# Schematic_v20.net
KiCad netlist of a schematic drawn in EAGLE
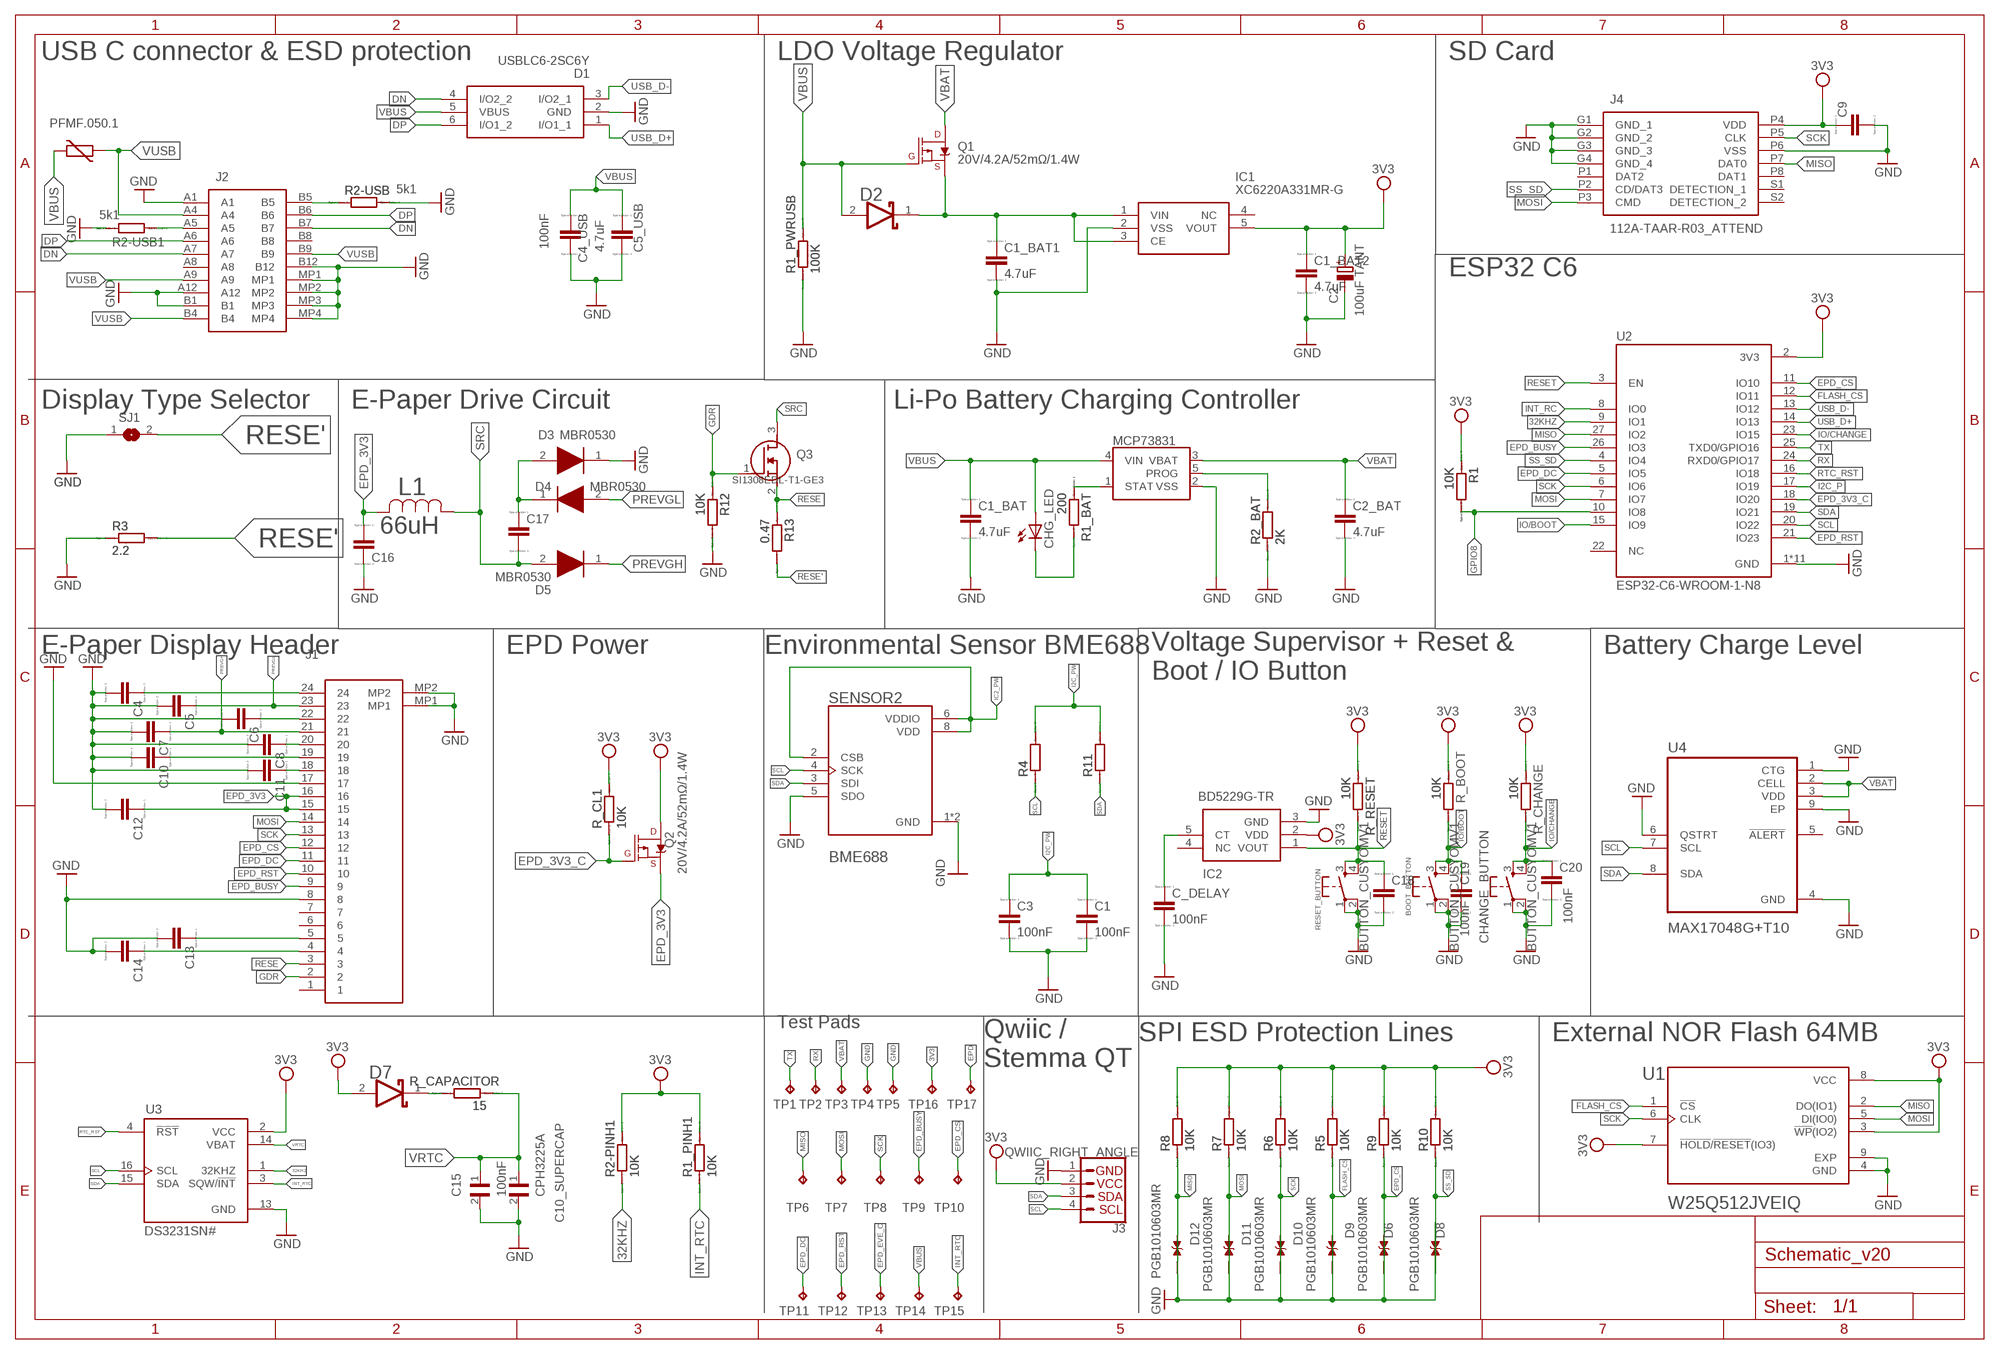
[diagram p0: schematic, sheet 1]

(export (version "E")
  (design (tool "Eeschema 10.0.6"))
  (components
    (comp (ref "BOOT_BUTTON")
      (value "BUTTON_CUSYOMV1")
      (footprint "eagle-import:MYBUTTON")
      (libsource (lib "eagle-import") (part "BUTTON_CUSYOMV1"))
    )
    (comp (ref "C1")
      (value "100nF")
      (footprint "eagle-import:ESP32_WROVER_EAGLE-LTSPICE_C0402")
      (libsource (lib "eagle-import") (part "ESP32_WROVER_EAGLE-LTSPICE_CC0402"))
    )
    (comp (ref "C1_BAT")
      (value "4.7uF")
      (footprint "eagle-import:ESP32_WROVER_EAGLE-LTSPICE_C0402")
      (libsource (lib "eagle-import") (part "ESP32_WROVER_EAGLE-LTSPICE_CC0402"))
    )
    (comp (ref "C1_BAT1")
      (value "4.7uF")
      (footprint "eagle-import:ESP32_WROVER_EAGLE-LTSPICE_C0402")
      (libsource (lib "eagle-import") (part "ESP32_WROVER_EAGLE-LTSPICE_CC0402"))
    )
    (comp (ref "C1_BAT2")
      (value "4.7uF")
      (footprint "eagle-import:ESP32_WROVER_EAGLE-LTSPICE_C0402")
      (libsource (lib "eagle-import") (part "ESP32_WROVER_EAGLE-LTSPICE_CC0402"))
    )
    (comp (ref "C2")
      (value "100uF TANT")
      (footprint "eagle-import:RCL_CT3528")
      (libsource (lib "eagle-import") (part "RCL_CPOL-EUCT3528"))
    )
    (comp (ref "C2_BAT")
      (value "4.7uF")
      (footprint "eagle-import:ESP32_WROVER_EAGLE-LTSPICE_C0402")
      (libsource (lib "eagle-import") (part "ESP32_WROVER_EAGLE-LTSPICE_CC0402"))
    )
    (comp (ref "C3")
      (value "100nF")
      (footprint "eagle-import:ESP32_WROVER_EAGLE-LTSPICE_C0402")
      (libsource (lib "eagle-import") (part "ESP32_WROVER_EAGLE-LTSPICE_CC0402"))
    )
    (comp (ref "C4")
      (value "ESP32_WROVER_EAGLE-LTSPICE_CC0402")
      (footprint "eagle-import:ESP32_WROVER_EAGLE-LTSPICE_C0402")
      (libsource (lib "eagle-import") (part "ESP32_WROVER_EAGLE-LTSPICE_CC0402"))
    )
    (comp (ref "C4_USB")
      (value "100nF")
      (footprint "eagle-import:ESP32_WROVER_EAGLE-LTSPICE_C0402")
      (libsource (lib "eagle-import") (part "ESP32_WROVER_EAGLE-LTSPICE_CC0402"))
    )
    (comp (ref "C5")
      (value "ESP32_WROVER_EAGLE-LTSPICE_CC0402")
      (footprint "eagle-import:ESP32_WROVER_EAGLE-LTSPICE_C0402")
      (libsource (lib "eagle-import") (part "ESP32_WROVER_EAGLE-LTSPICE_CC0402"))
    )
    (comp (ref "C5_USB")
      (value "4.7uF")
      (footprint "eagle-import:ESP32_WROVER_EAGLE-LTSPICE_C0402")
      (libsource (lib "eagle-import") (part "ESP32_WROVER_EAGLE-LTSPICE_CC0402"))
    )
    (comp (ref "C6")
      (value "ESP32_WROVER_EAGLE-LTSPICE_CC0402")
      (footprint "eagle-import:ESP32_WROVER_EAGLE-LTSPICE_C0402")
      (libsource (lib "eagle-import") (part "ESP32_WROVER_EAGLE-LTSPICE_CC0402"))
    )
    (comp (ref "C7")
      (value "ESP32_WROVER_EAGLE-LTSPICE_CC0402")
      (footprint "eagle-import:ESP32_WROVER_EAGLE-LTSPICE_C0402")
      (libsource (lib "eagle-import") (part "ESP32_WROVER_EAGLE-LTSPICE_CC0402"))
    )
    (comp (ref "C8")
      (value "ESP32_WROVER_EAGLE-LTSPICE_CC0402")
      (footprint "eagle-import:ESP32_WROVER_EAGLE-LTSPICE_C0402")
      (libsource (lib "eagle-import") (part "ESP32_WROVER_EAGLE-LTSPICE_CC0402"))
    )
    (comp (ref "C9")
      (value "ESP32_WROVER_EAGLE-LTSPICE_CC0402")
      (footprint "eagle-import:ESP32_WROVER_EAGLE-LTSPICE_C0402")
      (libsource (lib "eagle-import") (part "ESP32_WROVER_EAGLE-LTSPICE_CC0402"))
    )
    (comp (ref "C10")
      (value "ESP32_WROVER_EAGLE-LTSPICE_CC0402")
      (footprint "eagle-import:ESP32_WROVER_EAGLE-LTSPICE_C0402")
      (libsource (lib "eagle-import") (part "ESP32_WROVER_EAGLE-LTSPICE_CC0402"))
    )
    (comp (ref "C10_SUPERCAP")
      (value "CPH3225A")
      (footprint "eagle-import:CAPCP3225X100N")
      (fields (field (name "MF") "Seiko Instruments"))
      (libsource (lib "eagle-import") (part "CPH3225A"))
    )
    (comp (ref "C11")
      (value "ESP32_WROVER_EAGLE-LTSPICE_CC0402")
      (footprint "eagle-import:ESP32_WROVER_EAGLE-LTSPICE_C0402")
      (libsource (lib "eagle-import") (part "ESP32_WROVER_EAGLE-LTSPICE_CC0402"))
    )
    (comp (ref "C12")
      (value "ESP32_WROVER_EAGLE-LTSPICE_CC0402")
      (footprint "eagle-import:ESP32_WROVER_EAGLE-LTSPICE_C0402")
      (libsource (lib "eagle-import") (part "ESP32_WROVER_EAGLE-LTSPICE_CC0402"))
    )
    (comp (ref "C13")
      (value "ESP32_WROVER_EAGLE-LTSPICE_CC0402")
      (footprint "eagle-import:ESP32_WROVER_EAGLE-LTSPICE_C0402")
      (libsource (lib "eagle-import") (part "ESP32_WROVER_EAGLE-LTSPICE_CC0402"))
    )
    (comp (ref "C14")
      (value "ESP32_WROVER_EAGLE-LTSPICE_CC0402")
      (footprint "eagle-import:ESP32_WROVER_EAGLE-LTSPICE_C0402")
      (libsource (lib "eagle-import") (part "ESP32_WROVER_EAGLE-LTSPICE_CC0402"))
    )
    (comp (ref "C15")
      (value "100nF")
      (footprint "eagle-import:CAPCP3225X100N")
      (fields (field (name "MF") "Seiko Instruments") (field (name "MP") "CPH3225A"))
      (libsource (lib "eagle-import") (part "CPH3225A"))
    )
    (comp (ref "C16")
      (value "ESP32_WROVER_EAGLE-LTSPICE_CC0402")
      (footprint "eagle-import:ESP32_WROVER_EAGLE-LTSPICE_C0402")
      (libsource (lib "eagle-import") (part "ESP32_WROVER_EAGLE-LTSPICE_CC0402"))
    )
    (comp (ref "C17")
      (value "ESP32_WROVER_EAGLE-LTSPICE_CC0402")
      (footprint "eagle-import:ESP32_WROVER_EAGLE-LTSPICE_C0402")
      (libsource (lib "eagle-import") (part "ESP32_WROVER_EAGLE-LTSPICE_CC0402"))
    )
    (comp (ref "C18")
      (value "ESP32_WROVER_EAGLE-LTSPICE_CC0402")
      (footprint "eagle-import:ESP32_WROVER_EAGLE-LTSPICE_C0402")
      (libsource (lib "eagle-import") (part "ESP32_WROVER_EAGLE-LTSPICE_CC0402"))
    )
    (comp (ref "C19")
      (value "100nF")
      (footprint "eagle-import:ESP32_WROVER_EAGLE-LTSPICE_C0402")
      (libsource (lib "eagle-import") (part "EAGLE-LTSPICE_CC0402"))
    )
    (comp (ref "C20")
      (value "100nF")
      (footprint "eagle-import:ESP32_WROVER_EAGLE-LTSPICE_C0402")
      (libsource (lib "eagle-import") (part "ESP32_WROVER_EAGLE-LTSPICE_CC0402"))
    )
    (comp (ref "CHANGE_BUTTON")
      (value "BUTTON_CUSYOMV1")
      (footprint "eagle-import:MYBUTTON")
      (libsource (lib "eagle-import") (part "BUTTON_CUSYOMV1"))
    )
    (comp (ref "CHG_LED")
      (value "ADAFRUIT_LEDCHIP-LED0603")
      (footprint "eagle-import:ADAFRUIT_CHIP-LED0603")
      (libsource (lib "eagle-import") (part "ADAFRUIT_LEDCHIP-LED0603"))
    )
    (comp (ref "C_DELAY")
      (value "100nF")
      (footprint "eagle-import:ESP32_WROVER_EAGLE-LTSPICE_C0402")
      (libsource (lib "eagle-import") (part "ESP32_WROVER_EAGLE-LTSPICE_CC0402"))
    )
    (comp (ref "D1")
      (value "USBLC6-2SC6Y")
      (footprint "eagle-import:SOT95P280X145-6N")
      (fields (field (name "MF") "STMicroelectronics"))
      (libsource (lib "eagle-import") (part "USBLC6-2SC6Y"))
    )
    (comp (ref "D2")
      (value "SD0805S020S1R0")
      (footprint "eagle-import:ESP32_WROVER_AVX---SD0805S020S1R0_AVX_SD0805S020S1R0_0")
      (fields
        (field (name "DIGIKEY_PART_NUMBER") "478-7800-1-ND")
        (field (name "MF") "AVX")
        (field (name "MOUSER_PART_NUMBER") "581-SD0805S020S1R0")
      )
      (libsource (lib "eagle-import") (part "ESP32_WROVER_AVX---SD0805S020S1R0_AVX_SD0805S020S1R0_0_0AVX_SD0805S020S1R0_0_0"))
    )
    (comp (ref "D3")
      (value "MBR0530")
      (footprint "eagle-import:SOD3716X135N")
      (fields (field (name "MF") "ON Semiconductor"))
      (libsource (lib "eagle-import") (part "MBR0530"))
    )
    (comp (ref "D4")
      (value "MBR0530")
      (footprint "eagle-import:SOD3716X135N")
      (fields (field (name "MF") "ON Semiconductor"))
      (libsource (lib "eagle-import") (part "MBR0530"))
    )
    (comp (ref "D5")
      (value "MBR0530")
      (footprint "eagle-import:SOD3716X135N")
      (fields (field (name "MF") "ON Semiconductor"))
      (libsource (lib "eagle-import") (part "MBR0530"))
    )
    (comp (ref "D6")
      (value "PGB1010603MR")
      (footprint "eagle-import:DIOC1608X36N")
      (fields (field (name "MF") "Littelfuse Inc."))
      (libsource (lib "eagle-import") (part "PGB1010603MR"))
    )
    (comp (ref "D7")
      (value "ESP32_WROVER_AVX---SD0805S020S1R0_AVX_SD0805S020S1R0_0_0AVX_SD0805S020S1R0_0_0")
      (footprint "eagle-import:ESP32_WROVER_AVX---SD0805S020S1R0_AVX_SD0805S020S1R0_0")
      (fields
        (field (name "DIGIKEY_PART_NUMBER") "478-7800-1-ND")
        (field (name "MF") "AVX")
        (field (name "MOUSER_PART_NUMBER") "581-SD0805S020S1R0")
      )
      (libsource (lib "eagle-import") (part "ESP32_WROVER_AVX---SD0805S020S1R0_AVX_SD0805S020S1R0_0_0AVX_SD0805S020S1R0_0_0"))
    )
    (comp (ref "D8")
      (value "PGB1010603MR")
      (footprint "eagle-import:DIOC1608X36N")
      (fields (field (name "MF") "Littelfuse Inc."))
      (libsource (lib "eagle-import") (part "PGB1010603MR"))
    )
    (comp (ref "D9")
      (value "PGB1010603MR")
      (footprint "eagle-import:DIOC1608X36N")
      (fields (field (name "MF") "Littelfuse Inc."))
      (libsource (lib "eagle-import") (part "PGB1010603MR"))
    )
    (comp (ref "D10")
      (value "PGB1010603MR")
      (footprint "eagle-import:DIOC1608X36N")
      (fields (field (name "MF") "Littelfuse Inc."))
      (libsource (lib "eagle-import") (part "PGB1010603MR"))
    )
    (comp (ref "D11")
      (value "PGB1010603MR")
      (footprint "eagle-import:DIOC1608X36N")
      (fields (field (name "MF") "Littelfuse Inc."))
      (libsource (lib "eagle-import") (part "PGB1010603MR"))
    )
    (comp (ref "D12")
      (value "PGB1010603MR")
      (footprint "eagle-import:DIOC1608X36N")
      (fields (field (name "MF") "Littelfuse Inc."))
      (libsource (lib "eagle-import") (part "PGB1010603MR"))
    )
    (comp (ref "IC1")
      (value "XC6220A331MR-G")
      (footprint "eagle-import:SOT95P280X120-5N")
      (fields (field (name "MOUSER_PART_NUMBER") "865-XC6220A331MR-G"))
      (libsource (lib "eagle-import") (part "XC6220A331MR-G"))
    )
    (comp (ref "IC2")
      (value "BD5229G-TR")
      (footprint "eagle-import:SOT95P280X125-5N")
      (fields (field (name "MOUSER_PART_NUMBER") "755-BD5229G-TR"))
      (libsource (lib "eagle-import") (part "BD5229G-TR"))
    )
    (comp (ref "J1")
      (value "FH34SRJ-24S-0.5SH_99_")
      (footprint "eagle-import:FH34SRJ24S05SH99")
      (fields
        (field (name "MANUFACTURER_PART_NUMBER") "FH34SRJ-24S-0.5SH(99)")
        (field (name "MOUSER_PART_NUMBER") "798-FH34SRJ24S05SH99")
      )
      (libsource (lib "eagle-import") (part "FH34SRJ-24S-0.5SH_99_"))
    )
    (comp (ref "J2")
      (value "SAMACSYS_PARTS_USB4110-GF-A")
      (footprint "eagle-import:SAMACSYS_PARTS_USB4110GFA")
      (fields
        (field (name "MANUFACTURER_PART_NUMBER") "USB4110-GF-A")
        (field (name "MOUSER_PART_NUMBER") "640-USB4110-GF-A")
      )
      (libsource (lib "eagle-import") (part "SAMACSYS_PARTS_USB4110-GF-A"))
    )
    (comp (ref "J3")
      (value "QWIIC_RIGHT_ANGLE")
      (footprint "eagle-import:JST04_1MM_RA")
      (libsource (lib "eagle-import") (part "QWIIC_CONNECTORJS-1MM"))
    )
    (comp (ref "J4")
      (value "112A-TAAR-R03_ATTEND")
      (footprint "eagle-import:112ATAARR03ATTEND")
      (fields (field (name "MANUFACTURER_PART_NUMBER") "112A-TAAR-R03 ATTEND"))
      (libsource (lib "eagle-import") (part "112A-TAAR-R03_ATTEND"))
    )
    (comp (ref "L1")
      (value "66uH")
      (footprint "eagle-import:IND_4828-WE-TPC_WRE")
      (fields
        (field (name "MANUFACTURER_PART_NUMBER") "744043680")
        (field (name "COPYRIGHT") "Copyright (C) 2024 Ultra Librarian. All rights reserved.")
      )
      (libsource (lib "eagle-import") (part "744043680IND_4828-WE-TPC_WRE"))
    )
    (comp (ref "MCP73831")
      (value "ESP32_WROVER_SPARKFUN-IC-POWER_MCP73831")
      (footprint "eagle-import:ESP32_WROVER_SPARKFUN-IC-POWER_SOT23-5")
      (libsource (lib "eagle-import") (part "ESP32_WROVER_SPARKFUN-IC-POWER_MCP73831"))
    )
    (comp (ref "Q1")
      (value "20V/4.2A/52mΩ/1.4W")
      (footprint "eagle-import:ESP32_WROVER_SPARKFUN-DISCRETESEMI_SOT23-3")
      (libsource (lib "eagle-import") (part "ESP32_WROVER_SPARKFUN-DISCRETESEMI_MOSFET_PCH-DMG2305UX-7"))
    )
    (comp (ref "Q2")
      (value "20V/4.2A/52mΩ/1.4W")
      (footprint "eagle-import:ESP32_WROVER_SPARKFUN-DISCRETESEMI_SOT23-3")
      (libsource (lib "eagle-import") (part "ESP32_WROVER_SPARKFUN-DISCRETESEMI_MOSFET_PCH-DMG2305UX-7"))
    )
    (comp (ref "Q3")
      (value "SI1308EDL-T1-GE3")
      (footprint "eagle-import:SOT65P210X110-3N")
      (fields (field (name "MF") "Vishay Siliconix"))
      (libsource (lib "eagle-import") (part "SI1308EDL-T1-GE3"))
    )
    (comp (ref "R1")
      (value "10K")
      (footprint "eagle-import:ESP32_WROVER_EAGLE-LTSPICE_R0402")
      (libsource (lib "eagle-import") (part "ESP32_WROVER_EAGLE-LTSPICE_RR0402"))
    )
    (comp (ref "R1_BAT")
      (value "200")
      (footprint "eagle-import:ESP32_WROVER_EAGLE-LTSPICE_R0402")
      (libsource (lib "eagle-import") (part "ESP32_WROVER_EAGLE-LTSPICE_RR0402"))
    )
    (comp (ref "R1_PINH1")
      (value "10K")
      (footprint "eagle-import:ESP32_WROVER_EAGLE-LTSPICE_R0402")
      (libsource (lib "eagle-import") (part "ESP32_WROVER_EAGLE-LTSPICE_RR0402"))
    )
    (comp (ref "R1_PWRUSB")
      (value "100K")
      (footprint "eagle-import:ESP32_WROVER_EAGLE-LTSPICE_R0402")
      (libsource (lib "eagle-import") (part "ESP32_WROVER_EAGLE-LTSPICE_RR0402"))
    )
    (comp (ref "R2")
      (value "PFMF.050.1")
      (footprint "eagle-import:ESP32C6_VARISTOR_CT_CN1812")
      (libsource (lib "eagle-import") (part "ESP32C6_VARISTORCN1812"))
    )
    (comp (ref "R2-PINH1")
      (value "10K")
      (footprint "eagle-import:ESP32_WROVER_EAGLE-LTSPICE_R0402")
      (libsource (lib "eagle-import") (part "ESP32_WROVER_EAGLE-LTSPICE_RR0402"))
    )
    (comp (ref "R2-USB")
      (value "5k1")
      (footprint "eagle-import:ESP32_WROVER_EAGLE-LTSPICE_R0402")
      (libsource (lib "eagle-import") (part "ESP32_WROVER_EAGLE-LTSPICE_RR0402"))
    )
    (comp (ref "R2-USB1")
      (value "5k1")
      (footprint "eagle-import:ESP32_WROVER_EAGLE-LTSPICE_R0402")
      (libsource (lib "eagle-import") (part "ESP32_WROVER_EAGLE-LTSPICE_RR0402"))
    )
    (comp (ref "R2_BAT")
      (value "2K")
      (footprint "eagle-import:ESP32_WROVER_EAGLE-LTSPICE_R0402")
      (libsource (lib "eagle-import") (part "ESP32_WROVER_EAGLE-LTSPICE_RR0402"))
    )
    (comp (ref "R3")
      (value "2.2")
      (footprint "eagle-import:ESP32_WROVER_EAGLE-LTSPICE_R0402")
      (libsource (lib "eagle-import") (part "ESP32_WROVER_EAGLE-LTSPICE_RR0402"))
    )
    (comp (ref "R4")
      (value "ESP32_WROVER_EAGLE-LTSPICE_RR0402")
      (footprint "eagle-import:ESP32_WROVER_EAGLE-LTSPICE_R0402")
      (libsource (lib "eagle-import") (part "ESP32_WROVER_EAGLE-LTSPICE_RR0402"))
    )
    (comp (ref "R5")
      (value "10K")
      (footprint "eagle-import:ESP32_WROVER_EAGLE-LTSPICE_R0402")
      (libsource (lib "eagle-import") (part "ESP32_WROVER_EAGLE-LTSPICE_RR0402"))
    )
    (comp (ref "R6")
      (value "10K")
      (footprint "eagle-import:ESP32_WROVER_EAGLE-LTSPICE_R0402")
      (libsource (lib "eagle-import") (part "ESP32_WROVER_EAGLE-LTSPICE_RR0402"))
    )
    (comp (ref "R7")
      (value "10K")
      (footprint "eagle-import:ESP32_WROVER_EAGLE-LTSPICE_R0402")
      (libsource (lib "eagle-import") (part "ESP32_WROVER_EAGLE-LTSPICE_RR0402"))
    )
    (comp (ref "R8")
      (value "10K")
      (footprint "eagle-import:ESP32_WROVER_EAGLE-LTSPICE_R0402")
      (libsource (lib "eagle-import") (part "ESP32_WROVER_EAGLE-LTSPICE_RR0402"))
    )
    (comp (ref "R9")
      (value "10K")
      (footprint "eagle-import:ESP32_WROVER_EAGLE-LTSPICE_R0402")
      (libsource (lib "eagle-import") (part "ESP32_WROVER_EAGLE-LTSPICE_RR0402"))
    )
    (comp (ref "R10")
      (value "10K")
      (footprint "eagle-import:ESP32_WROVER_EAGLE-LTSPICE_R0402")
      (libsource (lib "eagle-import") (part "ESP32_WROVER_EAGLE-LTSPICE_RR0402"))
    )
    (comp (ref "R11")
      (value "ESP32_WROVER_EAGLE-LTSPICE_RR0402")
      (footprint "eagle-import:ESP32_WROVER_EAGLE-LTSPICE_R0402")
      (libsource (lib "eagle-import") (part "ESP32_WROVER_EAGLE-LTSPICE_RR0402"))
    )
    (comp (ref "R12")
      (value "10K")
      (footprint "eagle-import:ESP32_WROVER_EAGLE-LTSPICE_R0402")
      (libsource (lib "eagle-import") (part "ESP32_WROVER_EAGLE-LTSPICE_RR0402"))
    )
    (comp (ref "R13")
      (value "0.47")
      (footprint "eagle-import:ESP32_WROVER_EAGLE-LTSPICE_R0402")
      (libsource (lib "eagle-import") (part "ESP32_WROVER_EAGLE-LTSPICE_RR0402"))
    )
    (comp (ref "RESET_BUTTON")
      (value "BUTTON_CUSYOMV1")
      (footprint "eagle-import:MYBUTTON")
      (libsource (lib "eagle-import") (part "BUTTON_CUSYOMV1"))
    )
    (comp (ref "R_BOOT")
      (value "10K")
      (footprint "eagle-import:ESP32_WROVER_EAGLE-LTSPICE_R0402")
      (libsource (lib "eagle-import") (part "ESP32_WROVER_EAGLE-LTSPICE_RR0402"))
    )
    (comp (ref "R_CAPACITOR")
      (value "15")
      (footprint "eagle-import:ESP32_WROVER_EAGLE-LTSPICE_R0402")
      (libsource (lib "eagle-import") (part "ESP32_WROVER_EAGLE-LTSPICE_RR0402"))
    )
    (comp (ref "R_CHANGE")
      (value "10K")
      (footprint "eagle-import:ESP32_WROVER_EAGLE-LTSPICE_R0402")
      (libsource (lib "eagle-import") (part "ESP32_WROVER_EAGLE-LTSPICE_RR0402"))
    )
    (comp (ref "R_CL1")
      (value "10K")
      (footprint "eagle-import:ESP32_WROVER_EAGLE-LTSPICE_R0402")
      (libsource (lib "eagle-import") (part "ESP32_WROVER_EAGLE-LTSPICE_RR0402"))
    )
    (comp (ref "R_RESET")
      (value "10K")
      (footprint "eagle-import:ESP32_WROVER_EAGLE-LTSPICE_R0402")
      (libsource (lib "eagle-import") (part "ESP32_WROVER_EAGLE-LTSPICE_RR0402"))
    )
    (comp (ref "SENSOR2")
      (value "BME688")
      (footprint "eagle-import:ESP32_WROVER_BME680_PSON80P300X300X100-8N")
      (fields (field (name "MF") "Bosch Sensortec") (field (name "MP") "BME680"))
      (libsource (lib "eagle-import") (part "ESP32_WROVER_BME680_BME680"))
    )
    (comp (ref "SJ1") (value "SJ") (footprint "eagle-import:SJ") (libsource (lib "eagle-import") (part "SJ")))
    (comp (ref "TP1")
      (value "TPTP20R")
      (footprint "eagle-import:TP20R")
      (libsource (lib "eagle-import") (part "TPTP20R"))
    )
    (comp (ref "TP2")
      (value "TPTP20R")
      (footprint "eagle-import:TP20R")
      (libsource (lib "eagle-import") (part "TPTP20R"))
    )
    (comp (ref "TP3")
      (value "TPTP20R")
      (footprint "eagle-import:TP20R")
      (libsource (lib "eagle-import") (part "TPTP20R"))
    )
    (comp (ref "TP4")
      (value "TPTP20R")
      (footprint "eagle-import:TP20R")
      (libsource (lib "eagle-import") (part "TPTP20R"))
    )
    (comp (ref "TP5")
      (value "TPTP20R")
      (footprint "eagle-import:TP20R")
      (libsource (lib "eagle-import") (part "TPTP20R"))
    )
    (comp (ref "TP6")
      (value "TPTP20R")
      (footprint "eagle-import:TP20R")
      (libsource (lib "eagle-import") (part "TPTP20R"))
    )
    (comp (ref "TP7")
      (value "TPTP20R")
      (footprint "eagle-import:TP20R")
      (libsource (lib "eagle-import") (part "TPTP20R"))
    )
    (comp (ref "TP8")
      (value "TPTP20R")
      (footprint "eagle-import:TP20R")
      (libsource (lib "eagle-import") (part "TPTP20R"))
    )
    (comp (ref "TP9")
      (value "TPTP20R")
      (footprint "eagle-import:TP20R")
      (libsource (lib "eagle-import") (part "TPTP20R"))
    )
    (comp (ref "TP10")
      (value "TPTP20R")
      (footprint "eagle-import:TP20R")
      (libsource (lib "eagle-import") (part "TPTP20R"))
    )
    (comp (ref "TP11")
      (value "TPTP20R")
      (footprint "eagle-import:TP20R")
      (libsource (lib "eagle-import") (part "TPTP20R"))
    )
    (comp (ref "TP12")
      (value "TPTP20R")
      (footprint "eagle-import:TP20R")
      (libsource (lib "eagle-import") (part "TPTP20R"))
    )
    (comp (ref "TP13")
      (value "TPTP20R")
      (footprint "eagle-import:TP20R")
      (libsource (lib "eagle-import") (part "TPTP20R"))
    )
    (comp (ref "TP14")
      (value "TPTP20R")
      (footprint "eagle-import:TP20R")
      (libsource (lib "eagle-import") (part "TPTP20R"))
    )
    (comp (ref "TP15")
      (value "TPTP20R")
      (footprint "eagle-import:TP20R")
      (libsource (lib "eagle-import") (part "TPTP20R"))
    )
    (comp (ref "TP16")
      (value "TPTP20R")
      (footprint "eagle-import:TP20R")
      (libsource (lib "eagle-import") (part "TPTP20R"))
    )
    (comp (ref "TP17")
      (value "TPTP20R")
      (footprint "eagle-import:TP20R")
      (libsource (lib "eagle-import") (part "TPTP20R"))
    )
    (comp (ref "U1")
      (value "W25Q512JVEIQ")
      (footprint "eagle-import:SON127P600X800X80-9N")
      (fields (field (name "MF") "Winbond Electronics"))
      (libsource (lib "eagle-import") (part "W25Q512JVEIQ"))
    )
    (comp (ref "U2")
      (value "ESP32-C6-WROOM-1-N8")
      (footprint "eagle-import:XCVR_ESP32-C6-WROOM-1-N8")
      (fields (field (name "MF") "Espressif Systems"))
      (libsource (lib "eagle-import") (part "ESP32-C6-WROOM-1-N8"))
    )
    (comp (ref "U3")
      (value "DS3231SN#")
      (footprint "eagle-import:SOIC127P1032X265-16N")
      (fields (field (name "MF") "Analog Devices"))
      (libsource (lib "eagle-import") (part "DS3231SN#"))
    )
    (comp (ref "U4")
      (value "MAX17048G+T10")
      (footprint "eagle-import:SON50P200X200X80-9N")
      (fields (field (name "MF") "Analog Devices"))
      (libsource (lib "eagle-import") (part "MAX17048G+T10"))
    )
  )
  (nets
    (net (code "1") (name "3V3") (class "Default")
      (node (ref "C1_BAT2") (pin "1") (pinfunction "1_1") (pintype "passive"))
      (node (ref "C2") (pin "+") (pinfunction "+_+") (pintype "passive"))
      (node (ref "C9") (pin "1") (pinfunction "1_1") (pintype "passive"))
      (node (ref "D7") (pin "2") (pinfunction "ANODE_2") (pintype "bidirectional"))
      (node (ref "IC1") (pin "5") (pinfunction "VOUT_5") (pintype "bidirectional"))
      (node (ref "IC2") (pin "2") (pinfunction "VDD_2") (pintype "bidirectional"))
      (node (ref "J3") (pin "2") (pinfunction "2_2") (pintype "power_in"))
      (node (ref "J4") (pin "P4") (pinfunction "VDD_P4") (pintype "bidirectional"))
      (node (ref "Q2") (pin "3") (pinfunction "D_3") (pintype "bidirectional"))
      (node (ref "R1") (pin "1") (pinfunction "1_1") (pintype "passive"))
      (node (ref "R10") (pin "2") (pinfunction "2_2") (pintype "passive"))
      (node (ref "R1_PINH1") (pin "2") (pinfunction "2_2") (pintype "passive"))
      (node (ref "R2-PINH1") (pin "2") (pinfunction "2_2") (pintype "passive"))
      (node (ref "R5") (pin "2") (pinfunction "2_2") (pintype "passive"))
      (node (ref "R6") (pin "2") (pinfunction "2_2") (pintype "passive"))
      (node (ref "R7") (pin "2") (pinfunction "2_2") (pintype "passive"))
      (node (ref "R8") (pin "2") (pinfunction "2_2") (pintype "passive"))
      (node (ref "R9") (pin "2") (pinfunction "2_2") (pintype "passive"))
      (node (ref "R_BOOT") (pin "1") (pinfunction "1_1") (pintype "passive"))
      (node (ref "R_CHANGE") (pin "1") (pinfunction "1_1") (pintype "passive"))
      (node (ref "R_CL1") (pin "2") (pinfunction "2_2") (pintype "passive"))
      (node (ref "R_RESET") (pin "1") (pinfunction "1_1") (pintype "passive"))
      (node (ref "TP16") (pin "TP") (pinfunction "TP_TP") (pintype "input"))
      (node (ref "U1") (pin "3") (pinfunction "~{WP}(IO2)_3") (pintype "bidirectional"))
      (node (ref "U1") (pin "7") (pinfunction "~{HOLD}/~{RESET}(IO3)_7") (pintype "bidirectional"))
      (node (ref "U1") (pin "8") (pinfunction "VCC_8") (pintype "power_in"))
      (node (ref "U2") (pin "2") (pinfunction "3V3_2") (pintype "power_in"))
      (node (ref "U3") (pin "2") (pinfunction "VCC_2") (pintype "power_in"))
    )
    (net (code "2") (name "32KHZ") (class "Default")
      (node (ref "R2-PINH1") (pin "1") (pinfunction "1_1") (pintype "passive"))
      (node (ref "U2") (pin "9") (pinfunction "IO1_9") (pintype "bidirectional"))
      (node (ref "U3") (pin "1") (pinfunction "32KHZ_1") (pintype "output"))
    )
    (net (code "3") (name "DN") (class "Default")
      (node (ref "D1") (pin "4") (pinfunction "I/O2_2_4") (pintype "bidirectional"))
      (node (ref "J2") (pin "A7") (pinfunction "A7_A7") (pintype "bidirectional"))
      (node (ref "J2") (pin "B7") (pinfunction "B7_B7") (pintype "bidirectional"))
    )
    (net (code "4") (name "DP") (class "Default")
      (node (ref "D1") (pin "6") (pinfunction "I/O1_2_6") (pintype "bidirectional"))
      (node (ref "J2") (pin "A6") (pinfunction "A6_A6") (pintype "bidirectional"))
      (node (ref "J2") (pin "B6") (pinfunction "B6_B6") (pintype "bidirectional"))
    )
    (net (code "5") (name "EPD") (class "Default")
      (node (ref "TP17") (pin "TP") (pinfunction "TP_TP") (pintype "input"))
    )
    (net (code "6") (name "EPD_3V3") (class "Default")
      (node (ref "C12") (pin "1") (pinfunction "1_1") (pintype "passive"))
      (node (ref "C16") (pin "1") (pinfunction "1_1") (pintype "passive"))
      (node (ref "J1") (pin "15") (pinfunction "15_15") (pintype "bidirectional"))
      (node (ref "J1") (pin "16") (pinfunction "16_16") (pintype "bidirectional"))
      (node (ref "L1") (pin "2") (pinfunction "2_2") (pintype "passive"))
      (node (ref "Q2") (pin "2") (pinfunction "S_2") (pintype "bidirectional"))
    )
    (net (code "7") (name "EPD_3V3_C") (class "Default")
      (node (ref "Q2") (pin "1") (pinfunction "G_1") (pintype "bidirectional"))
      (node (ref "R_CL1") (pin "1") (pinfunction "1_1") (pintype "passive"))
      (node (ref "U2") (pin "18") (pinfunction "IO20_18") (pintype "bidirectional"))
    )
    (net (code "8") (name "EPD_BUSY") (class "Default")
      (node (ref "J1") (pin "9") (pinfunction "9_9") (pintype "bidirectional"))
      (node (ref "TP9") (pin "TP") (pinfunction "TP_TP") (pintype "input"))
      (node (ref "U2") (pin "26") (pinfunction "IO3_26") (pintype "bidirectional"))
    )
    (net (code "9") (name "EPD_CS") (class "Default")
      (node (ref "D6") (pin "2") (pinfunction "2_2") (pintype "passive"))
      (node (ref "J1") (pin "12") (pinfunction "12_12") (pintype "bidirectional"))
      (node (ref "R9") (pin "1") (pinfunction "1_1") (pintype "passive"))
      (node (ref "TP10") (pin "TP") (pinfunction "TP_TP") (pintype "input"))
      (node (ref "U2") (pin "11") (pinfunction "IO10_11") (pintype "bidirectional"))
    )
    (net (code "10") (name "EPD_DC") (class "Default")
      (node (ref "J1") (pin "11") (pinfunction "11_11") (pintype "bidirectional"))
      (node (ref "TP11") (pin "TP") (pinfunction "TP_TP") (pintype "input"))
      (node (ref "U2") (pin "5") (pinfunction "IO5_5") (pintype "bidirectional"))
    )
    (net (code "11") (name "EPD_EVE_C") (class "Default")
      (node (ref "TP13") (pin "TP") (pinfunction "TP_TP") (pintype "input"))
    )
    (net (code "12") (name "EPD_RST") (class "Default")
      (node (ref "J1") (pin "10") (pinfunction "10_10") (pintype "bidirectional"))
      (node (ref "TP12") (pin "TP") (pinfunction "TP_TP") (pintype "input"))
      (node (ref "U2") (pin "21") (pinfunction "IO23_21") (pintype "bidirectional"))
    )
    (net (code "13") (name "FLASH_CS") (class "Default")
      (node (ref "D9") (pin "2") (pinfunction "2_2") (pintype "passive"))
      (node (ref "R5") (pin "1") (pinfunction "1_1") (pintype "passive"))
      (node (ref "U1") (pin "1") (pinfunction "~{CS}_1") (pintype "input"))
      (node (ref "U2") (pin "12") (pinfunction "IO11_12") (pintype "bidirectional"))
    )
    (net (code "14") (name "GDR") (class "Default")
      (node (ref "J1") (pin "2") (pinfunction "2_2") (pintype "bidirectional"))
      (node (ref "Q3") (pin "1") (pinfunction "G_1") (pintype "bidirectional"))
      (node (ref "R12") (pin "1") (pinfunction "1_1") (pintype "passive"))
    )
    (net (code "15") (name "GND") (class "Default")
      (node (ref "BOOT_BUTTON") (pin "1") (pinfunction "1_1") (pintype "passive"))
      (node (ref "BOOT_BUTTON") (pin "2") (pinfunction "2_2") (pintype "passive"))
      (node (ref "C1") (pin "2") (pinfunction "2_2") (pintype "passive"))
      (node (ref "C10") (pin "2") (pinfunction "2_2") (pintype "passive"))
      (node (ref "C10_SUPERCAP") (pin "2") (pinfunction "2_2") (pintype "passive"))
      (node (ref "C11") (pin "2") (pinfunction "2_2") (pintype "passive"))
      (node (ref "C12") (pin "2") (pinfunction "2_2") (pintype "passive"))
      (node (ref "C13") (pin "2") (pinfunction "2_2") (pintype "passive"))
      (node (ref "C14") (pin "2") (pinfunction "2_2") (pintype "passive"))
      (node (ref "C15") (pin "2") (pinfunction "2_2") (pintype "passive"))
      (node (ref "C16") (pin "2") (pinfunction "2_2") (pintype "passive"))
      (node (ref "C18") (pin "2") (pinfunction "2_2") (pintype "passive"))
      (node (ref "C19") (pin "2") (pinfunction "2_2") (pintype "passive"))
      (node (ref "C1_BAT") (pin "2") (pinfunction "2_2") (pintype "passive"))
      (node (ref "C1_BAT1") (pin "2") (pinfunction "2_2") (pintype "passive"))
      (node (ref "C1_BAT2") (pin "2") (pinfunction "2_2") (pintype "passive"))
      (node (ref "C2") (pin "-") (pinfunction "-_-") (pintype "passive"))
      (node (ref "C20") (pin "2") (pinfunction "2_2") (pintype "passive"))
      (node (ref "C2_BAT") (pin "2") (pinfunction "2_2") (pintype "passive"))
      (node (ref "C3") (pin "2") (pinfunction "2_2") (pintype "passive"))
      (node (ref "C4") (pin "2") (pinfunction "2_2") (pintype "passive"))
      (node (ref "C4_USB") (pin "2") (pinfunction "2_2") (pintype "passive"))
      (node (ref "C5") (pin "2") (pinfunction "2_2") (pintype "passive"))
      (node (ref "C5_USB") (pin "2") (pinfunction "2_2") (pintype "passive"))
      (node (ref "C6") (pin "2") (pinfunction "2_2") (pintype "passive"))
      (node (ref "C7") (pin "2") (pinfunction "2_2") (pintype "passive"))
      (node (ref "C8") (pin "2") (pinfunction "2_2") (pintype "passive"))
      (node (ref "C9") (pin "2") (pinfunction "2_2") (pintype "passive"))
      (node (ref "CHANGE_BUTTON") (pin "1") (pinfunction "1_1") (pintype "passive"))
      (node (ref "CHANGE_BUTTON") (pin "2") (pinfunction "2_2") (pintype "passive"))
      (node (ref "C_DELAY") (pin "2") (pinfunction "2_2") (pintype "passive"))
      (node (ref "D1") (pin "2") (pinfunction "GND_2") (pintype "bidirectional"))
      (node (ref "D10") (pin "1") (pinfunction "1_1") (pintype "passive"))
      (node (ref "D11") (pin "1") (pinfunction "1_1") (pintype "passive"))
      (node (ref "D12") (pin "1") (pinfunction "1_1") (pintype "passive"))
      (node (ref "D4") (pin "1") (pinfunction "K_1") (pintype "bidirectional"))
      (node (ref "D6") (pin "1") (pinfunction "1_1") (pintype "passive"))
      (node (ref "D8") (pin "1") (pinfunction "1_1") (pintype "passive"))
      (node (ref "D9") (pin "1") (pinfunction "1_1") (pintype "passive"))
      (node (ref "IC1") (pin "2") (pinfunction "VSS_2") (pintype "bidirectional"))
      (node (ref "IC2") (pin "3") (pinfunction "GND_3") (pintype "bidirectional"))
      (node (ref "J1") (pin "17") (pinfunction "17_17") (pintype "bidirectional"))
      (node (ref "J1") (pin "8") (pinfunction "8_8") (pintype "bidirectional"))
      (node (ref "J1") (pin "MP1") (pinfunction "MP1_MP1") (pintype "bidirectional"))
      (node (ref "J1") (pin "MP2") (pinfunction "MP2_MP2") (pintype "bidirectional"))
      (node (ref "J2") (pin "A1") (pinfunction "A1_A1") (pintype "bidirectional"))
      (node (ref "J2") (pin "A12") (pinfunction "A12_A12") (pintype "bidirectional"))
      (node (ref "J2") (pin "B1") (pinfunction "B1_B1") (pintype "bidirectional"))
      (node (ref "J2") (pin "B12") (pinfunction "B12_B12") (pintype "bidirectional"))
      (node (ref "J2") (pin "MP1") (pinfunction "MP1_MP1") (pintype "bidirectional"))
      (node (ref "J2") (pin "MP2") (pinfunction "MP2_MP2") (pintype "bidirectional"))
      (node (ref "J2") (pin "MP3") (pinfunction "MP3_MP3") (pintype "bidirectional"))
      (node (ref "J2") (pin "MP4") (pinfunction "MP4_MP4") (pintype "bidirectional"))
      (node (ref "J3") (pin "1") (pinfunction "1_1") (pintype "power_in"))
      (node (ref "J4") (pin "G1") (pinfunction "GND_1_G1") (pintype "bidirectional"))
      (node (ref "J4") (pin "G2") (pinfunction "GND_2_G2") (pintype "bidirectional"))
      (node (ref "J4") (pin "G3") (pinfunction "GND_3_G3") (pintype "bidirectional"))
      (node (ref "J4") (pin "G4") (pinfunction "GND_4_G4") (pintype "bidirectional"))
      (node (ref "J4") (pin "P6") (pinfunction "VSS_P6") (pintype "bidirectional"))
      (node (ref "MCP73831") (pin "2") (pinfunction "VSS_2") (pintype "power_in"))
      (node (ref "R12") (pin "2") (pinfunction "2_2") (pintype "passive"))
      (node (ref "R1_PWRUSB") (pin "1") (pinfunction "1_1") (pintype "passive"))
      (node (ref "R2-USB") (pin "2") (pinfunction "2_2") (pintype "passive"))
      (node (ref "R2-USB1") (pin "1") (pinfunction "1_1") (pintype "passive"))
      (node (ref "R2_BAT") (pin "1") (pinfunction "1_1") (pintype "passive"))
      (node (ref "R3") (pin "1") (pinfunction "1_1") (pintype "passive"))
      (node (ref "RESET_BUTTON") (pin "1") (pinfunction "1_1") (pintype "passive"))
      (node (ref "RESET_BUTTON") (pin "2") (pinfunction "2_2") (pintype "passive"))
      (node (ref "SENSOR2") (pin "1") (pinfunction "GND_1") (pintype "power_in"))
      (node (ref "SENSOR2") (pin "5") (pinfunction "SDO_5") (pintype "bidirectional"))
      (node (ref "SENSOR2") (pin "7") (pinfunction "GND_7") (pintype "power_in"))
      (node (ref "SJ1") (pin "1") (pinfunction "1_1") (pintype "passive"))
      (node (ref "TP4") (pin "TP") (pinfunction "TP_TP") (pintype "input"))
      (node (ref "TP5") (pin "TP") (pinfunction "TP_TP") (pintype "input"))
      (node (ref "U1") (pin "4") (pinfunction "GND_4") (pintype "power_in"))
      (node (ref "U1") (pin "9") (pinfunction "EXP_9") (pintype "passive"))
      (node (ref "U2") (pin "1") (pinfunction "GND_1") (pintype "power_in"))
      (node (ref "U2") (pin "28") (pinfunction "GND_28") (pintype "power_in"))
      (node (ref "U2") (pin "29_1") (pinfunction "GND_29_1") (pintype "power_in"))
      (node (ref "U2") (pin "29_2") (pinfunction "GND_29_2") (pintype "power_in"))
      (node (ref "U2") (pin "29_3") (pinfunction "GND_29_3") (pintype "power_in"))
      (node (ref "U2") (pin "29_4") (pinfunction "GND_29_4") (pintype "power_in"))
      (node (ref "U2") (pin "29_5") (pinfunction "GND_29_5") (pintype "power_in"))
      (node (ref "U2") (pin "29_6") (pinfunction "GND_29_6") (pintype "power_in"))
      (node (ref "U2") (pin "29_7") (pinfunction "GND_29_7") (pintype "power_in"))
      (node (ref "U2") (pin "29_8") (pinfunction "GND_29_8") (pintype "power_in"))
      (node (ref "U2") (pin "29_9") (pinfunction "GND_29_9") (pintype "power_in"))
      (node (ref "U3") (pin "13") (pinfunction "GND_13") (pintype "power_in"))
      (node (ref "U4") (pin "1") (pinfunction "CTG_1") (pintype "power_in"))
      (node (ref "U4") (pin "4") (pinfunction "GND_4") (pintype "power_in"))
      (node (ref "U4") (pin "6") (pinfunction "QSTRT_6") (pintype "input"))
      (node (ref "U4") (pin "9") (pinfunction "EP_9") (pintype "power_in"))
    )
    (net (code "16") (name "GPIO8") (class "Default")
      (node (ref "R1") (pin "2") (pinfunction "2_2") (pintype "passive"))
      (node (ref "U2") (pin "10") (pinfunction "IO8_10") (pintype "bidirectional"))
    )
    (net (code "17") (name "I2C_P") (class "Default")
      (node (ref "U2") (pin "17") (pinfunction "IO19_17") (pintype "bidirectional"))
    )
    (net (code "18") (name "I2C_PW") (class "Default")
      (node (ref "C1") (pin "1") (pinfunction "1_1") (pintype "passive"))
      (node (ref "C3") (pin "1") (pinfunction "1_1") (pintype "passive"))
      (node (ref "R11") (pin "2") (pinfunction "2_2") (pintype "passive"))
      (node (ref "R4") (pin "2") (pinfunction "2_2") (pintype "passive"))
    )
    (net (code "19") (name "IC2_PW") (class "Default")
      (node (ref "SENSOR2") (pin "2") (pinfunction "CSB_2") (pintype "input"))
      (node (ref "SENSOR2") (pin "6") (pinfunction "VDDIO_6") (pintype "power_in"))
      (node (ref "SENSOR2") (pin "8") (pinfunction "VDD_8") (pintype "power_in"))
    )
    (net (code "20") (name "INT_RC") (class "Default")
      (node (ref "U2") (pin "8") (pinfunction "IO0_8") (pintype "bidirectional"))
    )
    (net (code "21") (name "INT_RTC") (class "Default")
      (node (ref "R1_PINH1") (pin "1") (pinfunction "1_1") (pintype "passive"))
      (node (ref "TP15") (pin "TP") (pinfunction "TP_TP") (pintype "input"))
      (node (ref "U3") (pin "3") (pinfunction "SQW/~{INT}_3") (pintype "output"))
    )
    (net (code "22") (name "IO{slash}BOOT") (class "Default")
      (node (ref "BOOT_BUTTON") (pin "3") (pinfunction "3_3") (pintype "passive"))
      (node (ref "BOOT_BUTTON") (pin "4") (pinfunction "4_4") (pintype "passive"))
      (node (ref "C19") (pin "1") (pinfunction "1_1") (pintype "passive"))
      (node (ref "R_BOOT") (pin "2") (pinfunction "2_2") (pintype "passive"))
      (node (ref "U2") (pin "15") (pinfunction "IO9_15") (pintype "bidirectional"))
    )
    (net (code "23") (name "IO{slash}CHANGE") (class "Default")
      (node (ref "C20") (pin "1") (pinfunction "1_1") (pintype "passive"))
      (node (ref "CHANGE_BUTTON") (pin "3") (pinfunction "3_3") (pintype "passive"))
      (node (ref "CHANGE_BUTTON") (pin "4") (pinfunction "4_4") (pintype "passive"))
      (node (ref "R_CHANGE") (pin "2") (pinfunction "2_2") (pintype "passive"))
      (node (ref "U2") (pin "23") (pinfunction "IO15_23") (pintype "bidirectional"))
    )
    (net (code "24") (name "MISO") (class "Default")
      (node (ref "D12") (pin "2") (pinfunction "2_2") (pintype "passive"))
      (node (ref "J4") (pin "P7") (pinfunction "DAT0_P7") (pintype "bidirectional"))
      (node (ref "R8") (pin "1") (pinfunction "1_1") (pintype "passive"))
      (node (ref "TP6") (pin "TP") (pinfunction "TP_TP") (pintype "input"))
      (node (ref "U1") (pin "2") (pinfunction "DO(IO1)_2") (pintype "bidirectional"))
      (node (ref "U2") (pin "27") (pinfunction "IO2_27") (pintype "bidirectional"))
    )
    (net (code "25") (name "MOSI") (class "Default")
      (node (ref "D11") (pin "2") (pinfunction "2_2") (pintype "passive"))
      (node (ref "J1") (pin "14") (pinfunction "14_14") (pintype "bidirectional"))
      (node (ref "J4") (pin "P3") (pinfunction "CMD_P3") (pintype "bidirectional"))
      (node (ref "R7") (pin "1") (pinfunction "1_1") (pintype "passive"))
      (node (ref "TP7") (pin "TP") (pinfunction "TP_TP") (pintype "input"))
      (node (ref "U1") (pin "5") (pinfunction "DI(IO0)_5") (pintype "bidirectional"))
      (node (ref "U2") (pin "7") (pinfunction "IO7_7") (pintype "bidirectional"))
    )
    (net (code "26") (name "Net-(C4-Pad1)") (class "Default")
      (node (ref "C4") (pin "1") (pinfunction "1_1") (pintype "passive"))
      (node (ref "J1") (pin "24") (pinfunction "24_24") (pintype "bidirectional"))
    )
    (net (code "27") (name "Net-(C6-Pad1)") (class "Default")
      (node (ref "C6") (pin "1") (pinfunction "1_1") (pintype "passive"))
      (node (ref "J1") (pin "22") (pinfunction "22_22") (pintype "bidirectional"))
    )
    (net (code "28") (name "Net-(C8-Pad1)") (class "Default")
      (node (ref "C8") (pin "1") (pinfunction "1_1") (pintype "passive"))
      (node (ref "J1") (pin "20") (pinfunction "20_20") (pintype "bidirectional"))
    )
    (net (code "29") (name "Net-(C10-Pad1)") (class "Default")
      (node (ref "C10") (pin "1") (pinfunction "1_1") (pintype "passive"))
      (node (ref "J1") (pin "19") (pinfunction "19_19") (pintype "bidirectional"))
    )
    (net (code "30") (name "Net-(C11-Pad1)") (class "Default")
      (node (ref "C11") (pin "1") (pinfunction "1_1") (pintype "passive"))
      (node (ref "J1") (pin "18") (pinfunction "18_18") (pintype "bidirectional"))
    )
    (net (code "31") (name "Net-(C13-Pad1)") (class "Default")
      (node (ref "C13") (pin "1") (pinfunction "1_1") (pintype "passive"))
      (node (ref "J1") (pin "5") (pinfunction "5_5") (pintype "bidirectional"))
    )
    (net (code "32") (name "Net-(C14-Pad1)") (class "Default")
      (node (ref "C14") (pin "1") (pinfunction "1_1") (pintype "passive"))
      (node (ref "J1") (pin "4") (pinfunction "4_4") (pintype "bidirectional"))
    )
    (net (code "33") (name "Net-(CHG_LED-PadC)") (class "Default")
      (node (ref "CHG_LED") (pin "C") (pinfunction "C_C") (pintype "passive"))
      (node (ref "R1_BAT") (pin "2") (pinfunction "2_2") (pintype "passive"))
    )
    (net (code "34") (name "Net-(D2-CATHODE)") (class "Default")
      (node (ref "C1_BAT1") (pin "1") (pinfunction "1_1") (pintype "passive"))
      (node (ref "D2") (pin "1") (pinfunction "CATHODE_1") (pintype "bidirectional"))
      (node (ref "IC1") (pin "1") (pinfunction "VIN_1") (pintype "bidirectional"))
      (node (ref "IC1") (pin "3") (pinfunction "CE_3") (pintype "bidirectional"))
      (node (ref "Q1") (pin "2") (pinfunction "S_2") (pintype "bidirectional"))
    )
    (net (code "35") (name "Net-(D3-K)") (class "Default")
      (node (ref "C17") (pin "1") (pinfunction "1_1") (pintype "passive"))
      (node (ref "D3") (pin "1") (pinfunction "K_1") (pintype "bidirectional"))
      (node (ref "D4") (pin "2") (pinfunction "A_2") (pintype "bidirectional"))
    )
    (net (code "36") (name "Net-(D7-CATHODE)") (class "Default")
      (node (ref "D7") (pin "1") (pinfunction "CATHODE_1") (pintype "bidirectional"))
      (node (ref "R_CAPACITOR") (pin "2") (pinfunction "2_2") (pintype "passive"))
    )
    (net (code "37") (name "Net-(IC2-CT)") (class "Default")
      (node (ref "C_DELAY") (pin "1") (pinfunction "1_1") (pintype "passive"))
      (node (ref "IC2") (pin "5") (pinfunction "CT_5") (pintype "bidirectional"))
    )
    (net (code "38") (name "Net-(J2-PadA5)") (class "Default")
      (node (ref "J2") (pin "A5") (pinfunction "A5_A5") (pintype "bidirectional"))
      (node (ref "R2-USB1") (pin "2") (pinfunction "2_2") (pintype "passive"))
    )
    (net (code "39") (name "Net-(J2-PadB5)") (class "Default")
      (node (ref "J2") (pin "B5") (pinfunction "B5_B5") (pintype "bidirectional"))
      (node (ref "R2-USB") (pin "1") (pinfunction "1_1") (pintype "passive"))
    )
    (net (code "40") (name "Net-(MCP73831-PROG)") (class "Default")
      (node (ref "MCP73831") (pin "5") (pinfunction "PROG_5") (pintype "input"))
      (node (ref "R2_BAT") (pin "2") (pinfunction "2_2") (pintype "passive"))
    )
    (net (code "41") (name "Net-(MCP73831-STAT)") (class "Default")
      (node (ref "MCP73831") (pin "1") (pinfunction "STAT_1") (pintype "output"))
      (node (ref "R1_BAT") (pin "1") (pinfunction "1_1") (pintype "passive"))
    )
    (net (code "42") (name "PREVGH") (class "Default")
      (node (ref "C7") (pin "1") (pinfunction "1_1") (pintype "passive"))
      (node (ref "D5") (pin "1") (pinfunction "K_1") (pintype "bidirectional"))
      (node (ref "J1") (pin "21") (pinfunction "21_21") (pintype "bidirectional"))
    )
    (net (code "43") (name "PREVGL") (class "Default")
      (node (ref "C5") (pin "1") (pinfunction "1_1") (pintype "passive"))
      (node (ref "D3") (pin "2") (pinfunction "A_2") (pintype "bidirectional"))
      (node (ref "J1") (pin "23") (pinfunction "23_23") (pintype "bidirectional"))
    )
    (net (code "44") (name "RESE") (class "Default")
      (node (ref "J1") (pin "3") (pinfunction "3_3") (pintype "bidirectional"))
      (node (ref "Q3") (pin "2") (pinfunction "S_2") (pintype "bidirectional"))
      (node (ref "R13") (pin "1") (pinfunction "1_1") (pintype "passive"))
    )
    (net (code "45") (name "RESE'") (class "Default")
      (node (ref "R13") (pin "2") (pinfunction "2_2") (pintype "passive"))
      (node (ref "R3") (pin "2") (pinfunction "2_2") (pintype "passive"))
      (node (ref "SJ1") (pin "2") (pinfunction "2_2") (pintype "passive"))
    )
    (net (code "46") (name "RESET") (class "Default")
      (node (ref "C18") (pin "1") (pinfunction "1_1") (pintype "passive"))
      (node (ref "IC2") (pin "1") (pinfunction "VOUT_1") (pintype "bidirectional"))
      (node (ref "RESET_BUTTON") (pin "3") (pinfunction "3_3") (pintype "passive"))
      (node (ref "RESET_BUTTON") (pin "4") (pinfunction "4_4") (pintype "passive"))
      (node (ref "R_RESET") (pin "2") (pinfunction "2_2") (pintype "passive"))
      (node (ref "U2") (pin "3") (pinfunction "EN_3") (pintype "input"))
    )
    (net (code "47") (name "RTC_RST") (class "Default")
      (node (ref "U2") (pin "16") (pinfunction "IO18_16") (pintype "bidirectional"))
      (node (ref "U3") (pin "4") (pinfunction "~{RST}_4") (pintype "input"))
    )
    (net (code "48") (name "RX") (class "Default")
      (node (ref "TP2") (pin "TP") (pinfunction "TP_TP") (pintype "input"))
      (node (ref "U2") (pin "24") (pinfunction "RXD0/GPIO17_24") (pintype "bidirectional"))
    )
    (net (code "49") (name "SCK") (class "Default")
      (node (ref "D10") (pin "2") (pinfunction "2_2") (pintype "passive"))
      (node (ref "J1") (pin "13") (pinfunction "13_13") (pintype "bidirectional"))
      (node (ref "J4") (pin "P5") (pinfunction "CLK_P5") (pintype "bidirectional"))
      (node (ref "R6") (pin "1") (pinfunction "1_1") (pintype "passive"))
      (node (ref "TP8") (pin "TP") (pinfunction "TP_TP") (pintype "input"))
      (node (ref "U1") (pin "6") (pinfunction "CLK_6") (pintype "input"))
      (node (ref "U2") (pin "6") (pinfunction "IO6_6") (pintype "bidirectional"))
    )
    (net (code "50") (name "SCL") (class "Default")
      (node (ref "J3") (pin "4") (pinfunction "4_4") (pintype "passive"))
      (node (ref "R4") (pin "1") (pinfunction "1_1") (pintype "passive"))
      (node (ref "SENSOR2") (pin "4") (pinfunction "SCK_4") (pintype "input"))
      (node (ref "U2") (pin "20") (pinfunction "IO22_20") (pintype "bidirectional"))
      (node (ref "U3") (pin "16") (pinfunction "SCL_16") (pintype "input"))
      (node (ref "U4") (pin "7") (pinfunction "SCL_7") (pintype "input"))
    )
    (net (code "51") (name "SDA") (class "Default")
      (node (ref "J3") (pin "3") (pinfunction "3_3") (pintype "passive"))
      (node (ref "R11") (pin "1") (pinfunction "1_1") (pintype "passive"))
      (node (ref "SENSOR2") (pin "3") (pinfunction "SDI_3") (pintype "bidirectional"))
      (node (ref "U2") (pin "19") (pinfunction "IO21_19") (pintype "bidirectional"))
      (node (ref "U3") (pin "15") (pinfunction "SDA_15") (pintype "bidirectional"))
      (node (ref "U4") (pin "8") (pinfunction "SDA_8") (pintype "bidirectional"))
    )
    (net (code "52") (name "SRC") (class "Default")
      (node (ref "C17") (pin "2") (pinfunction "2_2") (pintype "passive"))
      (node (ref "D5") (pin "2") (pinfunction "A_2") (pintype "bidirectional"))
      (node (ref "L1") (pin "1") (pinfunction "1_1") (pintype "passive"))
      (node (ref "Q3") (pin "3") (pinfunction "D_3") (pintype "bidirectional"))
    )
    (net (code "53") (name "SS_SD") (class "Default")
      (node (ref "D8") (pin "2") (pinfunction "2_2") (pintype "passive"))
      (node (ref "J4") (pin "P2") (pinfunction "CD/DAT3_P2") (pintype "bidirectional"))
      (node (ref "R10") (pin "1") (pinfunction "1_1") (pintype "passive"))
      (node (ref "U2") (pin "4") (pinfunction "IO4_4") (pintype "bidirectional"))
    )
    (net (code "54") (name "TX") (class "Default")
      (node (ref "TP1") (pin "TP") (pinfunction "TP_TP") (pintype "input"))
      (node (ref "U2") (pin "25") (pinfunction "TXD0/GPIO16_25") (pintype "bidirectional"))
    )
    (net (code "55") (name "USB_D+") (class "Default")
      (node (ref "D1") (pin "1") (pinfunction "I/O1_1_1") (pintype "bidirectional"))
      (node (ref "U2") (pin "14") (pinfunction "IO13_14") (pintype "bidirectional"))
    )
    (net (code "56") (name "USB_D-") (class "Default")
      (node (ref "D1") (pin "3") (pinfunction "I/O2_1_3") (pintype "bidirectional"))
      (node (ref "U2") (pin "13") (pinfunction "IO12_13") (pintype "bidirectional"))
    )
    (net (code "57") (name "VBAT") (class "Default")
      (node (ref "C2_BAT") (pin "1") (pinfunction "1_1") (pintype "passive"))
      (node (ref "MCP73831") (pin "3") (pinfunction "VBAT_3") (pintype "power_in"))
      (node (ref "Q1") (pin "3") (pinfunction "D_3") (pintype "bidirectional"))
      (node (ref "TP3") (pin "TP") (pinfunction "TP_TP") (pintype "input"))
      (node (ref "U4") (pin "2") (pinfunction "CELL_2") (pintype "power_in"))
      (node (ref "U4") (pin "3") (pinfunction "VDD_3") (pintype "power_in"))
    )
    (net (code "58") (name "VBUS") (class "Default")
      (node (ref "C1_BAT") (pin "1") (pinfunction "1_1") (pintype "passive"))
      (node (ref "C4_USB") (pin "1") (pinfunction "1_1") (pintype "passive"))
      (node (ref "C5_USB") (pin "1") (pinfunction "1_1") (pintype "passive"))
      (node (ref "CHG_LED") (pin "A") (pinfunction "A_A") (pintype "passive"))
      (node (ref "D1") (pin "5") (pinfunction "VBUS_5") (pintype "bidirectional"))
      (node (ref "D2") (pin "2") (pinfunction "ANODE_2") (pintype "bidirectional"))
      (node (ref "MCP73831") (pin "4") (pinfunction "VIN_4") (pintype "power_in"))
      (node (ref "Q1") (pin "1") (pinfunction "G_1") (pintype "bidirectional"))
      (node (ref "R1_PWRUSB") (pin "2") (pinfunction "2_2") (pintype "passive"))
      (node (ref "R2") (pin "1") (pinfunction "1_1") (pintype "passive"))
      (node (ref "TP14") (pin "TP") (pinfunction "TP_TP") (pintype "input"))
    )
    (net (code "59") (name "VRTC") (class "Default")
      (node (ref "C10_SUPERCAP") (pin "1") (pinfunction "1_1") (pintype "passive"))
      (node (ref "C15") (pin "1") (pinfunction "1_1") (pintype "passive"))
      (node (ref "R_CAPACITOR") (pin "1") (pinfunction "1_1") (pintype "passive"))
      (node (ref "U3") (pin "14") (pinfunction "VBAT_14") (pintype "power_in"))
    )
    (net (code "60") (name "VUSB") (class "Default")
      (node (ref "J2") (pin "A4") (pinfunction "A4_A4") (pintype "bidirectional"))
      (node (ref "J2") (pin "A9") (pinfunction "A9_A9") (pintype "bidirectional"))
      (node (ref "J2") (pin "B4") (pinfunction "B4_B4") (pintype "bidirectional"))
      (node (ref "J2") (pin "B9") (pinfunction "B9_B9") (pintype "bidirectional"))
      (node (ref "R2") (pin "2") (pinfunction "2_2") (pintype "passive"))
    )
    (net (code "61") (name "unconnected-(IC1-NC-Pad4)") (class "Default")
      (node (ref "IC1") (pin "4") (pinfunction "NC_4") (pintype "no_connect"))
    )
    (net (code "62") (name "unconnected-(IC2-NC-Pad4)") (class "Default")
      (node (ref "IC2") (pin "4") (pinfunction "NC_4") (pintype "no_connect"))
    )
    (net (code "63") (name "unconnected-(J1-Pad1)") (class "Default")
      (node (ref "J1") (pin "1") (pinfunction "1_1") (pintype "bidirectional"))
    )
    (net (code "64") (name "unconnected-(J1-Pad6)") (class "Default")
      (node (ref "J1") (pin "6") (pinfunction "6_6") (pintype "bidirectional"))
    )
    (net (code "65") (name "unconnected-(J1-Pad7)") (class "Default")
      (node (ref "J1") (pin "7") (pinfunction "7_7") (pintype "bidirectional"))
    )
    (net (code "66") (name "unconnected-(J2-PadA8)") (class "Default")
      (node (ref "J2") (pin "A8") (pinfunction "A8_A8") (pintype "bidirectional"))
    )
    (net (code "67") (name "unconnected-(J2-PadB8)") (class "Default")
      (node (ref "J2") (pin "B8") (pinfunction "B8_B8") (pintype "bidirectional"))
    )
    (net (code "68") (name "unconnected-(J4-DAT1-PadP8)") (class "Default")
      (node (ref "J4") (pin "P8") (pinfunction "DAT1_P8") (pintype "bidirectional"))
    )
    (net (code "69") (name "unconnected-(J4-DAT2-PadP1)") (class "Default")
      (node (ref "J4") (pin "P1") (pinfunction "DAT2_P1") (pintype "bidirectional"))
    )
    (net (code "70") (name "unconnected-(J4-DETECTION_1-PadS1)") (class "Default")
      (node (ref "J4") (pin "S1") (pinfunction "DETECTION_1_S1") (pintype "bidirectional"))
    )
    (net (code "71") (name "unconnected-(J4-DETECTION_2-PadS2)") (class "Default")
      (node (ref "J4") (pin "S2") (pinfunction "DETECTION_2_S2") (pintype "bidirectional"))
    )
    (net (code "72") (name "unconnected-(U2-NC-Pad22)") (class "Default")
      (node (ref "U2") (pin "22") (pinfunction "NC_22") (pintype "no_connect"))
    )
    (net (code "73") (name "unconnected-(U4-~{ALERT}-Pad5)") (class "Default")
      (node (ref "U4") (pin "5") (pinfunction "~{ALERT}_5") (pintype "output"))
    )
  )
)
